# Solar_Charger_Adafruit.net
KiCad netlist of a schematic drawn in EAGLE
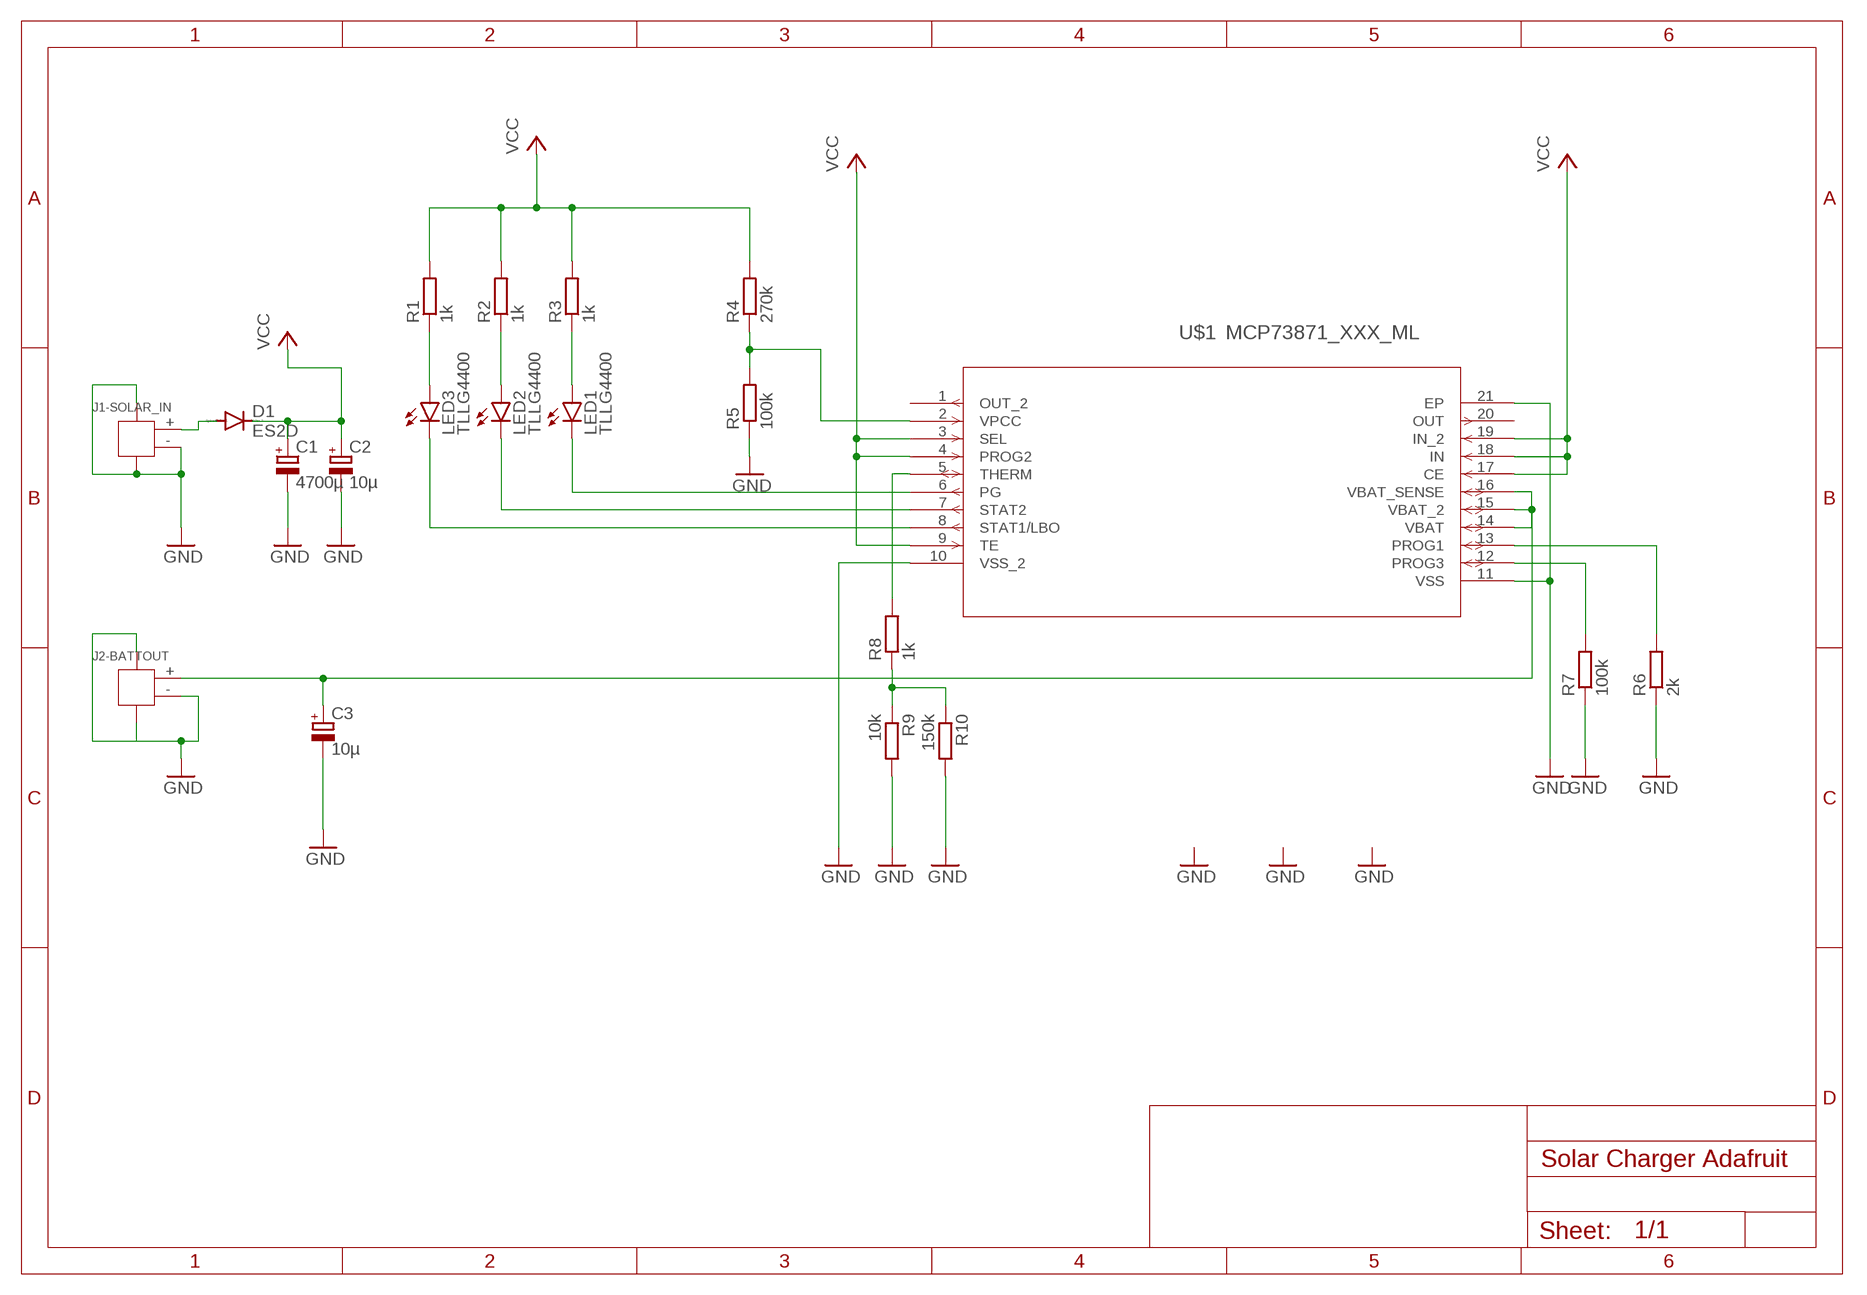
[diagram p0: schematic, sheet 1]

(export (version "E")
  (design (tool "Eeschema 10.0.6"))
  (components
    (comp (ref "C1")
      (value "4700µ")
      (footprint "eagle-import:C_6032-28R")
      (libsource (lib "eagle-import") (part "CPOL-EUC/6032-28R"))
    )
    (comp (ref "C2")
      (value "10µ")
      (footprint "eagle-import:C_6032-28R")
      (libsource (lib "eagle-import") (part "CPOL-EUC/6032-28R"))
    )
    (comp (ref "C3")
      (value "10µ")
      (footprint "eagle-import:C_6032-28R")
      (libsource (lib "eagle-import") (part "CPOL-EUC/6032-28R"))
    )
    (comp (ref "D1")
      (value "ES2D")
      (footprint "eagle-import:SMB")
      (libsource (lib "eagle-import") (part "ES2D"))
    )
    (comp (ref "J1-SOLAR_IN")
      (value "CONN-HEADER-SMD-PH-SIDE-(2P-2.0MM)")
      (footprint "eagle-import:HW2-SMD-2.0-90D")
      (libsource (lib "eagle-import") (part "CONN-HEADER-SMD-PH-SIDE-(2P-2.0MM)"))
    )
    (comp (ref "J2-BATTOUT")
      (value "CONN-HEADER-SMD-PH-SIDE-(2P-2.0MM)")
      (footprint "eagle-import:HW2-SMD-2.0-90D")
      (libsource (lib "eagle-import") (part "CONN-HEADER-SMD-PH-SIDE-(2P-2.0MM)"))
    )
    (comp (ref "LED1")
      (value "TLLG4400")
      (footprint "eagle-import:LED3MM")
      (fields (field (name "MF") "VISHAY SEMICONDUCTOR"))
      (libsource (lib "eagle-import") (part "TLLG4400"))
    )
    (comp (ref "LED2")
      (value "TLLG4400")
      (footprint "eagle-import:LED3MM")
      (fields (field (name "MF") "VISHAY SEMICONDUCTOR"))
      (libsource (lib "eagle-import") (part "TLLG4400"))
    )
    (comp (ref "LED3")
      (value "TLLG4400")
      (footprint "eagle-import:LED3MM")
      (fields (field (name "MF") "VISHAY SEMICONDUCTOR"))
      (libsource (lib "eagle-import") (part "TLLG4400"))
    )
    (comp (ref "R1")
      (value "1k")
      (footprint "eagle-import:R0603")
      (libsource (lib "eagle-import") (part "R-EU_R0603"))
    )
    (comp (ref "R2")
      (value "1k")
      (footprint "eagle-import:R0603")
      (libsource (lib "eagle-import") (part "R-EU_R0603"))
    )
    (comp (ref "R3")
      (value "1k")
      (footprint "eagle-import:R0603")
      (libsource (lib "eagle-import") (part "R-EU_R0603"))
    )
    (comp (ref "R4")
      (value "270k")
      (footprint "eagle-import:R0603")
      (libsource (lib "eagle-import") (part "R-EU_R0603"))
    )
    (comp (ref "R5")
      (value "100k")
      (footprint "eagle-import:R0603")
      (libsource (lib "eagle-import") (part "R-EU_R0603"))
    )
    (comp (ref "R6")
      (value "2k")
      (footprint "eagle-import:R0603")
      (libsource (lib "eagle-import") (part "R-EU_R0603"))
    )
    (comp (ref "R7")
      (value "100k")
      (footprint "eagle-import:R0603")
      (libsource (lib "eagle-import") (part "R-EU_R0603"))
    )
    (comp (ref "R8")
      (value "1k")
      (footprint "eagle-import:R0603")
      (libsource (lib "eagle-import") (part "R-EU_R0603"))
    )
    (comp (ref "R9")
      (value "10k")
      (footprint "eagle-import:R0603")
      (libsource (lib "eagle-import") (part "R-EU_R0603"))
    )
    (comp (ref "R10")
      (value "150k")
      (footprint "eagle-import:R0603")
      (libsource (lib "eagle-import") (part "R-EU_R0603"))
    )
    (comp (ref "U$1")
      (value "MCP73871_XXX_ML")
      (footprint "eagle-import:QFN20_4X4MC")
      (libsource (lib "eagle-import") (part "MCP73871_XXX_ML"))
    )
  )
  (nets
    (net (code "1") (name "GND") (class "Default")
      (node (ref "C1") (pin "-") (pinfunction "-_-") (pintype "passive"))
      (node (ref "C2") (pin "-") (pinfunction "-_-") (pintype "passive"))
      (node (ref "C3") (pin "-") (pinfunction "-_-") (pintype "passive"))
      (node (ref "J1-SOLAR_IN") (pin "-") (pinfunction "2_-") (pintype "bidirectional"))
      (node (ref "J1-SOLAR_IN") (pin "3") (pinfunction "3_3") (pintype "bidirectional"))
      (node (ref "J1-SOLAR_IN") (pin "4") (pinfunction "4_4") (pintype "bidirectional"))
      (node (ref "J2-BATTOUT") (pin "-") (pinfunction "2_-") (pintype "bidirectional"))
      (node (ref "J2-BATTOUT") (pin "3") (pinfunction "3_3") (pintype "bidirectional"))
      (node (ref "J2-BATTOUT") (pin "4") (pinfunction "4_4") (pintype "bidirectional"))
      (node (ref "R10") (pin "2") (pinfunction "2_2") (pintype "passive"))
      (node (ref "R5") (pin "1") (pinfunction "1_1") (pintype "passive"))
      (node (ref "R6") (pin "1") (pinfunction "1_1") (pintype "passive"))
      (node (ref "R7") (pin "1") (pinfunction "1_1") (pintype "passive"))
      (node (ref "R9") (pin "2") (pinfunction "2_2") (pintype "passive"))
      (node (ref "U$1") (pin "10") (pinfunction "VSS_2_10") (pintype "power_in"))
      (node (ref "U$1") (pin "11") (pinfunction "VSS_11") (pintype "power_in"))
      (node (ref "U$1") (pin "21") (pinfunction "EP_21") (pintype "passive"))
    )
    (net (code "2") (name "Net-(J1-SOLAR_IN-1)") (class "Default")
      (node (ref "D1") (pin "A") (pinfunction "A_A") (pintype "passive"))
      (node (ref "J1-SOLAR_IN") (pin "+") (pinfunction "1_+") (pintype "bidirectional"))
    )
    (net (code "3") (name "Net-(J2-BATTOUT-1)") (class "Default")
      (node (ref "C3") (pin "+") (pinfunction "+_+") (pintype "passive"))
      (node (ref "J2-BATTOUT") (pin "+") (pinfunction "1_+") (pintype "bidirectional"))
      (node (ref "U$1") (pin "14") (pinfunction "VBAT_14") (pintype "bidirectional"))
      (node (ref "U$1") (pin "15") (pinfunction "VBAT_2_15") (pintype "bidirectional"))
      (node (ref "U$1") (pin "16") (pinfunction "VBAT_SENSE_16") (pintype "bidirectional"))
    )
    (net (code "4") (name "Net-(LED1-C)") (class "Default")
      (node (ref "LED1") (pin "K") (pinfunction "C_K") (pintype "passive"))
      (node (ref "U$1") (pin "6") (pinfunction "PG_6") (pintype "output"))
    )
    (net (code "5") (name "Net-(LED1-PadA)") (class "Default")
      (node (ref "LED1") (pin "A") (pinfunction "A_A") (pintype "passive"))
      (node (ref "R3") (pin "1") (pinfunction "1_1") (pintype "passive"))
    )
    (net (code "6") (name "Net-(LED2-C)") (class "Default")
      (node (ref "LED2") (pin "K") (pinfunction "C_K") (pintype "passive"))
      (node (ref "U$1") (pin "7") (pinfunction "STAT2_7") (pintype "output"))
    )
    (net (code "7") (name "Net-(LED2-PadA)") (class "Default")
      (node (ref "LED2") (pin "A") (pinfunction "A_A") (pintype "passive"))
      (node (ref "R2") (pin "1") (pinfunction "1_1") (pintype "passive"))
    )
    (net (code "8") (name "Net-(LED3-C)") (class "Default")
      (node (ref "LED3") (pin "K") (pinfunction "C_K") (pintype "passive"))
      (node (ref "U$1") (pin "8") (pinfunction "STAT1/LBO_8") (pintype "output"))
    )
    (net (code "9") (name "Net-(LED3-PadA)") (class "Default")
      (node (ref "LED3") (pin "A") (pinfunction "A_A") (pintype "passive"))
      (node (ref "R1") (pin "1") (pinfunction "1_1") (pintype "passive"))
    )
    (net (code "10") (name "Net-(R10-Pad1)") (class "Default")
      (node (ref "R10") (pin "1") (pinfunction "1_1") (pintype "passive"))
      (node (ref "R8") (pin "1") (pinfunction "1_1") (pintype "passive"))
      (node (ref "R9") (pin "1") (pinfunction "1_1") (pintype "passive"))
    )
    (net (code "11") (name "Net-(U$1-PROG1)") (class "Default")
      (node (ref "R6") (pin "2") (pinfunction "2_2") (pintype "passive"))
      (node (ref "U$1") (pin "13") (pinfunction "PROG1_13") (pintype "bidirectional"))
    )
    (net (code "12") (name "Net-(U$1-PROG3)") (class "Default")
      (node (ref "R7") (pin "2") (pinfunction "2_2") (pintype "passive"))
      (node (ref "U$1") (pin "12") (pinfunction "PROG3_12") (pintype "bidirectional"))
    )
    (net (code "13") (name "Net-(U$1-THERM)") (class "Default")
      (node (ref "R8") (pin "2") (pinfunction "2_2") (pintype "passive"))
      (node (ref "U$1") (pin "5") (pinfunction "THERM_5") (pintype "bidirectional"))
    )
    (net (code "14") (name "Net-(U$1-VPCC)") (class "Default")
      (node (ref "R4") (pin "1") (pinfunction "1_1") (pintype "passive"))
      (node (ref "R5") (pin "2") (pinfunction "2_2") (pintype "passive"))
      (node (ref "U$1") (pin "2") (pinfunction "VPCC_2") (pintype "input"))
    )
    (net (code "15") (name "VCC") (class "Default")
      (node (ref "C1") (pin "+") (pinfunction "+_+") (pintype "passive"))
      (node (ref "C2") (pin "+") (pinfunction "+_+") (pintype "passive"))
      (node (ref "D1") (pin "C") (pinfunction "C_C") (pintype "passive"))
      (node (ref "R1") (pin "2") (pinfunction "2_2") (pintype "passive"))
      (node (ref "R2") (pin "2") (pinfunction "2_2") (pintype "passive"))
      (node (ref "R3") (pin "2") (pinfunction "2_2") (pintype "passive"))
      (node (ref "R4") (pin "2") (pinfunction "2_2") (pintype "passive"))
      (node (ref "U$1") (pin "17") (pinfunction "CE_17") (pintype "input"))
      (node (ref "U$1") (pin "18") (pinfunction "IN_18") (pintype "input"))
      (node (ref "U$1") (pin "19") (pinfunction "IN_2_19") (pintype "input"))
      (node (ref "U$1") (pin "3") (pinfunction "SEL_3") (pintype "input"))
      (node (ref "U$1") (pin "4") (pinfunction "PROG2_4") (pintype "input"))
      (node (ref "U$1") (pin "9") (pinfunction "TE_9") (pintype "input"))
    )
    (net (code "16") (name "unconnected-(U$1-OUT-Pad20)") (class "Default")
      (node (ref "U$1") (pin "20") (pinfunction "OUT_20") (pintype "output"))
    )
    (net (code "17") (name "unconnected-(U$1-OUT_2-Pad1)") (class "Default")
      (node (ref "U$1") (pin "1") (pinfunction "OUT_2_1") (pintype "output"))
    )
  )
)
